# Buck-Boost_Controller.net
KiCad netlist of a schematic drawn in Altium Designer
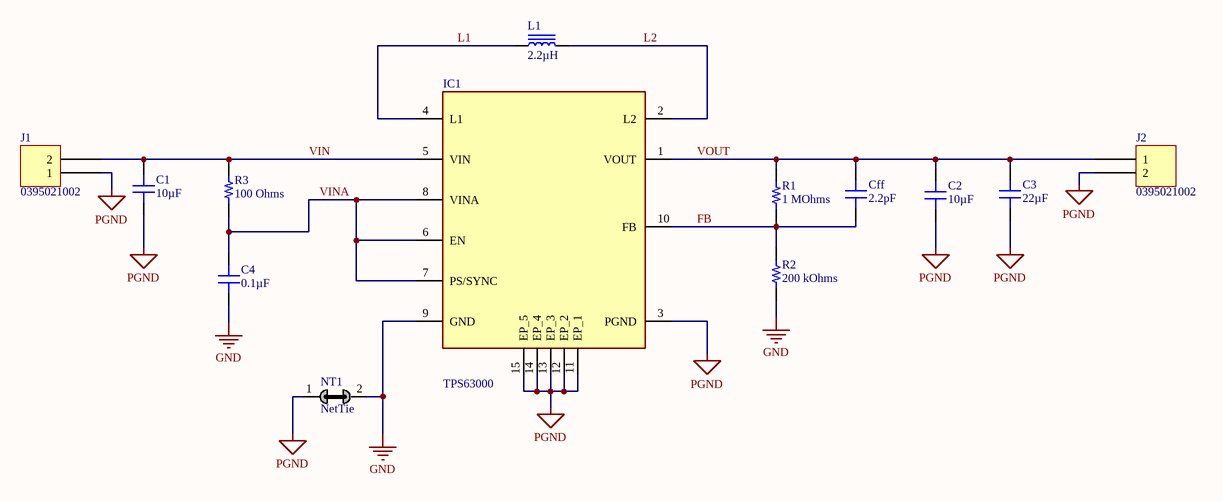
[diagram p0: Buck-Boost Controller.SchDoc]

(export (version "E")
  (design (tool "Eeschema 10.0.6"))
  (components
    (comp (ref "C1")
      (value "10µF")
      (footprint "CAP 0805_2012")
      (description "CAP CER 10UF 10V X7R 0805")
      (fields
        (field (name "PART NUMBER") "C2012X7R1A106M125AC")
        (field (name "MANUFACTURER") "TDK Corporation")
      )
      (libsource (lib "Celestial Altium Library - altium_library") (part "Capacitor"))
    )
    (comp (ref "C2")
      (value "10µF")
      (footprint "CAP 0805_2012")
      (description "CAP CER 10UF 10V X7R 0805")
      (fields
        (field (name "PART NUMBER") "C2012X7R1A106M125AC")
        (field (name "MANUFACTURER") "TDK Corporation")
      )
      (libsource (lib "Celestial Altium Library - altium_library") (part "Capacitor"))
    )
    (comp (ref "C3")
      (value "22µF")
      (footprint "CAP 0805_2012")
      (description "CAP CER 22UF 10V X5R 0805")
      (fields
        (field (name "PART NUMBER") "CL21A226MPCLRNC")
        (field (name "MANUFACTURER") "Samsung Electro-Mechanics")
      )
      (libsource (lib "Celestial Altium Library - altium_library") (part "Capacitor"))
    )
    (comp (ref "C4")
      (value "0.1µF")
      (footprint "CAP 0805_2012")
      (description "CAP CER 0.1UF 50V X8R 0805")
      (fields
        (field (name "PART NUMBER") "GCM21BR91H104KA37L")
        (field (name "MANUFACTURER") "Murata Electronics")
      )
      (libsource (lib "Celestial Altium Library - altium_library") (part "Capacitor"))
    )
    (comp (ref "Cff")
      (value "2.2pF")
      (footprint "CAP 0805_2012")
      (description "CAP CER 2.2PF 100V NP0 0805")
      (fields (field (name "PART NUMBER") "C0805C229C1GAC7800") (field (name "MANUFACTURER") "KEMET"))
      (libsource (lib "Celestial Altium Library - altium_library") (part "Capacitor"))
    )
    (comp (ref "IC1")
      (value "TPS63000")
      (footprint "PCB_Lib:TPS63002DRCR")
      (description "Switching Regulator, Current-mode, 2A, 1500kHz Switching Freq-Max, PDSO10")
      (fields
        (field (name "MANUFACTURER_PART_NUMBER") "TPS63002DRCR")
        (field (name "MOUSER PART NUMBER") "595-TPS63002DRCR")
      )
      (libsource (lib "SCH_Lib") (part "TPS63000DRCR"))
    )
    (comp (ref "J1")
      (value "0395021002")
      (footprint "MOLEX 395021002")
      (description "TERM BLOCK HDR 2POS 90DEG 3.5MM")
      (fields (field (name "MANUFACTURER") "Molex"))
      (libsource (lib "") (part "2 Pin_1"))
    )
    (comp (ref "J2")
      (value "0395021002")
      (footprint "MOLEX 395021002")
      (description "TERM BLOCK HDR 2POS 90DEG 3.5MM")
      (fields (field (name "MANUFACTURER") "Molex"))
      (libsource (lib "Celestial Altium Library - altium_library") (part "2 Pin"))
    )
    (comp (ref "L1")
      (value "2.2µH")
      (footprint "MURATA LQH31")
      (description "FIXED IND 2.2UH 430MA 410 MOHM")
      (fields
        (field (name "PART NUMBER") "LQH31CN2R2M03L")
        (field (name "MANUFACTURER") "Murata Electronics")
      )
      (libsource (lib "Celestial Altium Library - altium_library") (part "Inductor"))
    )
    (comp (ref "NT1")
      (value "NetTie")
      (footprint "NetTie_Narrow2")
      (libsource (lib "SCH_Lib") (part "NetTie"))
    )
    (comp (ref "R1")
      (value "1 MOhms")
      (footprint "RES 0805_2012")
      (description "RES SMD 1M OHM 1% 1/8W 0805")
      (fields (field (name "PART NUMBER") "CRCW08051M00FKEB") (field (name "MANUFACTURER") "Vishay Dale"))
      (libsource (lib "Celestial Altium Library - altium_library") (part "Resistor"))
    )
    (comp (ref "R2")
      (value "200 kOhms")
      (footprint "RES 0805_2012")
      (description "RES 200K OHM 0.5% 1/8W 0805")
      (fields
        (field (name "PART NUMBER") "ERA-6AED204V")
        (field (name "MANUFACTURER") "Panasonic Electronic Components")
      )
      (libsource (lib "Celestial Altium Library - altium_library") (part "Resistor"))
    )
    (comp (ref "R3")
      (value "100 Ohms")
      (footprint "RES 0805_2012")
      (description "RES 100 OHM 1% 1/8W 0805")
      (fields (field (name "PART NUMBER") "ASC0805-100RF1") (field (name "MANUFACTURER") "Riedon"))
      (libsource (lib "Celestial Altium Library - altium_library") (part "Resistor"))
    )
  )
  (nets
    (net (code "2") (name "/FB") (class "Default")
      (node (ref "Cff") (pin "1") (pinfunction "1_1") (pintype "passive"))
      (node (ref "IC1") (pin "10") (pinfunction "FB_10") (pintype "passive"))
      (node (ref "R1") (pin "1") (pinfunction "1_1") (pintype "passive"))
      (node (ref "R2") (pin "2") (pinfunction "2_2") (pintype "passive"))
    )
    (net (code "3") (name "/L1") (class "Default")
      (node (ref "IC1") (pin "4") (pinfunction "L1_4") (pintype "passive"))
      (node (ref "L1") (pin "1") (pinfunction "1_1") (pintype "passive"))
    )
    (net (code "4") (name "/L2") (class "Default")
      (node (ref "IC1") (pin "2") (pinfunction "L2_2") (pintype "passive"))
      (node (ref "L1") (pin "2") (pinfunction "2_2") (pintype "passive"))
    )
    (net (code "5") (name "/VIN") (class "Default")
      (node (ref "C1") (pin "2") (pinfunction "2_2") (pintype "passive"))
      (node (ref "IC1") (pin "5") (pinfunction "VIN_5") (pintype "passive"))
      (node (ref "J1") (pin "2") (pinfunction "2_2") (pintype "passive"))
      (node (ref "R3") (pin "2") (pinfunction "2_2") (pintype "passive"))
    )
    (net (code "6") (name "/VINA") (class "Default")
      (node (ref "C4") (pin "2") (pinfunction "2_2") (pintype "passive"))
      (node (ref "IC1") (pin "6") (pinfunction "EN_6") (pintype "passive"))
      (node (ref "IC1") (pin "7") (pinfunction "PS/SYNC_7") (pintype "passive"))
      (node (ref "IC1") (pin "8") (pinfunction "VINA_8") (pintype "passive"))
      (node (ref "R3") (pin "1") (pinfunction "1_1") (pintype "passive"))
    )
    (net (code "7") (name "/VOUT") (class "Default")
      (node (ref "C2") (pin "2") (pinfunction "2_2") (pintype "passive"))
      (node (ref "C3") (pin "2") (pinfunction "2_2") (pintype "passive"))
      (node (ref "Cff") (pin "2") (pinfunction "2_2") (pintype "passive"))
      (node (ref "IC1") (pin "1") (pinfunction "VOUT_1") (pintype "passive"))
      (node (ref "J2") (pin "1") (pinfunction "1_1") (pintype "passive"))
      (node (ref "R1") (pin "2") (pinfunction "2_2") (pintype "passive"))
    )
    (net (code "8") (name "GND") (class "Default")
      (node (ref "C4") (pin "1") (pinfunction "1_1") (pintype "passive"))
      (node (ref "IC1") (pin "9") (pinfunction "GND_9") (pintype "passive"))
      (node (ref "NT1") (pin "2") (pinfunction "2_2") (pintype "passive"))
      (node (ref "R2") (pin "1") (pinfunction "1_1") (pintype "passive"))
    )
    (net (code "9") (name "PGND") (class "Default")
      (node (ref "C1") (pin "1") (pinfunction "1_1") (pintype "passive"))
      (node (ref "C2") (pin "1") (pinfunction "1_1") (pintype "passive"))
      (node (ref "C3") (pin "1") (pinfunction "1_1") (pintype "passive"))
      (node (ref "IC1") (pin "11") (pinfunction "EP_1_11") (pintype "passive"))
      (node (ref "IC1") (pin "12") (pinfunction "EP_2_12") (pintype "passive"))
      (node (ref "IC1") (pin "13") (pinfunction "EP_3_13") (pintype "passive"))
      (node (ref "IC1") (pin "14") (pinfunction "EP_4_14") (pintype "passive"))
      (node (ref "IC1") (pin "15") (pinfunction "EP_5_15") (pintype "passive"))
      (node (ref "IC1") (pin "3") (pinfunction "PGND_3") (pintype "passive"))
      (node (ref "J1") (pin "1") (pinfunction "1_1") (pintype "passive"))
      (node (ref "J2") (pin "2") (pinfunction "2_2") (pintype "passive"))
      (node (ref "NT1") (pin "1") (pinfunction "1_1") (pintype "passive"))
    )
  )
)
